# TopfieldClock.net
KiCad netlist of a schematic drawn in EAGLE
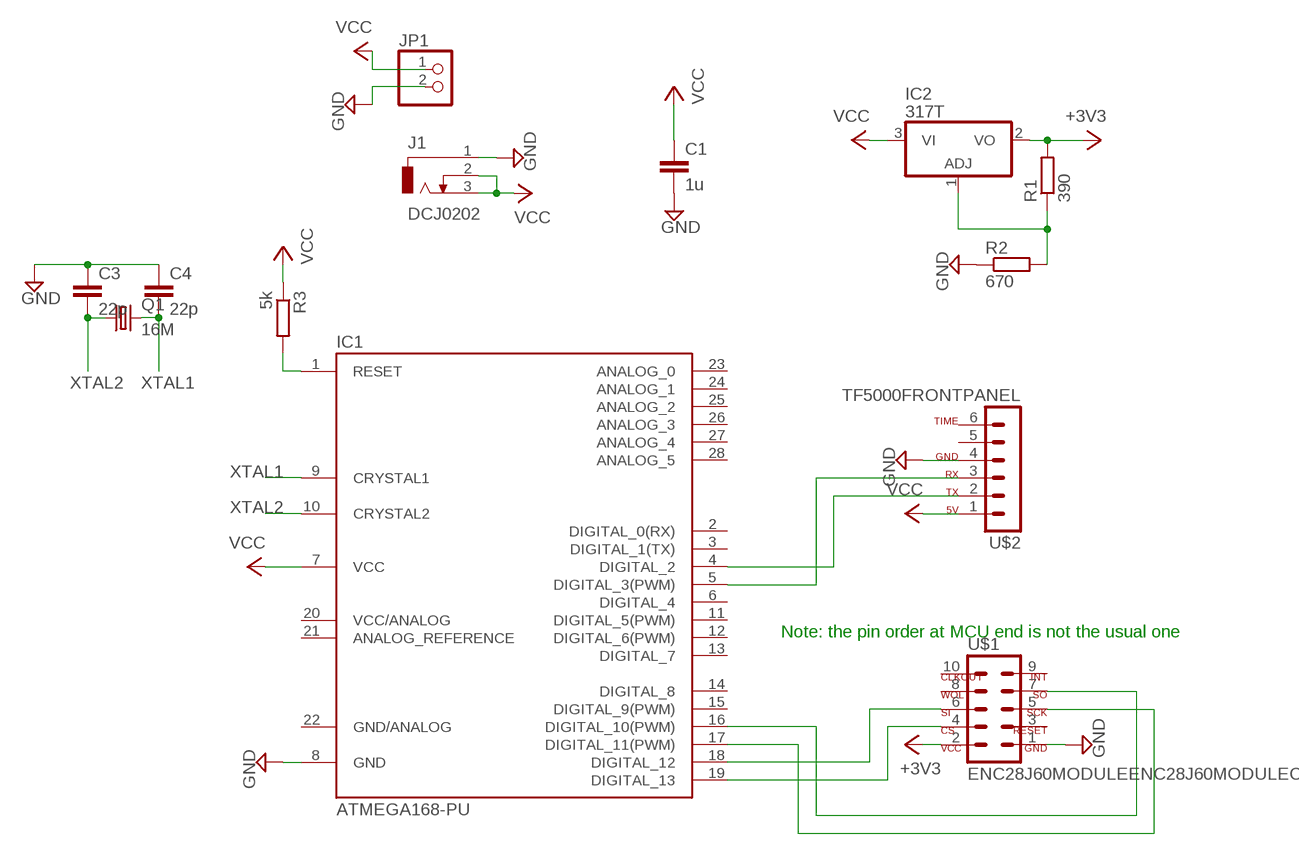
[diagram p0: schematic, sheet 1]

(export (version "E")
  (design (tool "Eeschema 10.0.6"))
  (components
    (comp (ref "C1")
      (value "1u")
      (footprint "eagle-import:C025-024X044")
      (libsource (lib "eagle-import") (part "C-EU025-024X044"))
    )
    (comp (ref "C3")
      (value "22p")
      (footprint "eagle-import:C025-024X044")
      (libsource (lib "eagle-import") (part "C-EU025-024X044"))
    )
    (comp (ref "C4")
      (value "22p")
      (footprint "eagle-import:C025-024X044")
      (libsource (lib "eagle-import") (part "C-EU025-024X044"))
    )
    (comp (ref "IC1")
      (value "ATMEGA168-PU")
      (footprint "eagle-import:DIL28-3")
      (libsource (lib "eagle-import") (part "ATMEGA168-PU"))
    )
    (comp (ref "IC2")
      (value "317T")
      (footprint "eagle-import:TO220H")
      (libsource (lib "eagle-import") (part "317T"))
    )
    (comp (ref "J1")
      (value "DCJ0202")
      (footprint "eagle-import:DCJ0202")
      (libsource (lib "eagle-import") (part "DCJ0202"))
    )
    (comp (ref "JP1")
      (value "PINHD-1X2/90")
      (footprint "eagle-import:1X02_90")
      (libsource (lib "eagle-import") (part "PINHD-1X2/90"))
    )
    (comp (ref "Q1")
      (value "16M")
      (footprint "eagle-import:HC18U-V")
      (libsource (lib "eagle-import") (part "CRYSTALHC18U-V"))
    )
    (comp (ref "R1")
      (value "390")
      (footprint "eagle-import:0204_7")
      (libsource (lib "eagle-import") (part "R-EU_0204/7"))
    )
    (comp (ref "R2")
      (value "670")
      (footprint "eagle-import:0204_7")
      (libsource (lib "eagle-import") (part "R-EU_0204/7"))
    )
    (comp (ref "R3")
      (value "5k")
      (footprint "eagle-import:0204_7")
      (libsource (lib "eagle-import") (part "R-EU_0204/7"))
    )
    (comp (ref "U$1")
      (value "ENC28J60MODULEENC28J60MODULECONN")
      (footprint "eagle-import:ENC28J60MODULECONN")
      (libsource (lib "eagle-import") (part "ENC28J60MODULEENC28J60MODULECONN"))
    )
    (comp (ref "U$2")
      (value "TF5000FRONTPANEL")
      (footprint "eagle-import:MA06-1")
      (libsource (lib "eagle-import") (part "TF5000FRONTPANEL"))
    )
  )
  (nets
    (net (code "1") (name "+3V3") (class "Default")
      (node (ref "IC2") (pin "2") (pinfunction "VO_2") (pintype "passive"))
      (node (ref "R1") (pin "2") (pinfunction "2_2") (pintype "passive"))
      (node (ref "U$1") (pin "2") (pinfunction "VCC_2") (pintype "passive"))
    )
    (net (code "2") (name "/GND{slash}ANALOG") (class "Default")
      (node (ref "IC1") (pin "22") (pinfunction "GND/ANALOG_22") (pintype "power_in"))
    )
    (net (code "3") (name "/XTAL1") (class "Default")
      (node (ref "C4") (pin "2") (pinfunction "2_2") (pintype "passive"))
      (node (ref "IC1") (pin "9") (pinfunction "CRYSTAL1_9") (pintype "bidirectional"))
      (node (ref "Q1") (pin "2") (pinfunction "2_2") (pintype "passive"))
    )
    (net (code "4") (name "/XTAL2") (class "Default")
      (node (ref "C3") (pin "2") (pinfunction "2_2") (pintype "passive"))
      (node (ref "IC1") (pin "10") (pinfunction "CRYSTAL2_10") (pintype "bidirectional"))
      (node (ref "Q1") (pin "1") (pinfunction "1_1") (pintype "passive"))
    )
    (net (code "5") (name "GND") (class "Default")
      (node (ref "C1") (pin "2") (pinfunction "2_2") (pintype "passive"))
      (node (ref "C3") (pin "1") (pinfunction "1_1") (pintype "passive"))
      (node (ref "C4") (pin "1") (pinfunction "1_1") (pintype "passive"))
      (node (ref "IC1") (pin "8") (pinfunction "GND_8") (pintype "power_in"))
      (node (ref "J1") (pin "1") (pinfunction "1_1") (pintype "passive"))
      (node (ref "JP1") (pin "2") (pinfunction "2_2") (pintype "passive"))
      (node (ref "R2") (pin "1") (pinfunction "1_1") (pintype "passive"))
      (node (ref "U$1") (pin "1") (pinfunction "GND_1") (pintype "passive"))
      (node (ref "U$2") (pin "4") (pinfunction "YELLOW_GND_4") (pintype "passive"))
    )
    (net (code "6") (name "Net-(IC1-DIGITAL_2)") (class "Default")
      (node (ref "IC1") (pin "4") (pinfunction "DIGITAL_2_4") (pintype "bidirectional"))
      (node (ref "U$2") (pin "2") (pinfunction "RED_OUTPUT_2") (pintype "passive"))
    )
    (net (code "7") (name "Net-(IC1-DIGITAL_3(PWM))") (class "Default")
      (node (ref "IC1") (pin "5") (pinfunction "DIGITAL_3(PWM)_5") (pintype "bidirectional"))
      (node (ref "U$2") (pin "3") (pinfunction "ORANGE_INPUT_3") (pintype "passive"))
    )
    (net (code "8") (name "Net-(IC1-DIGITAL_10(PWM))") (class "Default")
      (node (ref "IC1") (pin "16") (pinfunction "DIGITAL_10(PWM)_16") (pintype "bidirectional"))
      (node (ref "U$1") (pin "7") (pinfunction "SO_7") (pintype "passive"))
    )
    (net (code "9") (name "Net-(IC1-DIGITAL_11(PWM))") (class "Default")
      (node (ref "IC1") (pin "17") (pinfunction "DIGITAL_11(PWM)_17") (pintype "bidirectional"))
      (node (ref "U$1") (pin "5") (pinfunction "SCK_5") (pintype "passive"))
    )
    (net (code "10") (name "Net-(IC1-DIGITAL_12)") (class "Default")
      (node (ref "IC1") (pin "18") (pinfunction "DIGITAL_12_18") (pintype "bidirectional"))
      (node (ref "U$1") (pin "6") (pinfunction "SI_6") (pintype "passive"))
    )
    (net (code "11") (name "Net-(IC1-DIGITAL_13)") (class "Default")
      (node (ref "IC1") (pin "19") (pinfunction "DIGITAL_13_19") (pintype "bidirectional"))
      (node (ref "U$1") (pin "4") (pinfunction "CS_4") (pintype "passive"))
    )
    (net (code "12") (name "Net-(IC1-RESET)") (class "Default")
      (node (ref "IC1") (pin "1") (pinfunction "RESET_1") (pintype "bidirectional"))
      (node (ref "R3") (pin "2") (pinfunction "2_2") (pintype "passive"))
    )
    (net (code "13") (name "Net-(IC2-ADJ)") (class "Default")
      (node (ref "IC2") (pin "1") (pinfunction "ADJ_1") (pintype "input"))
      (node (ref "R1") (pin "1") (pinfunction "1_1") (pintype "passive"))
      (node (ref "R2") (pin "2") (pinfunction "2_2") (pintype "passive"))
    )
    (net (code "14") (name "VCC") (class "Default")
      (node (ref "C1") (pin "1") (pinfunction "1_1") (pintype "passive"))
      (node (ref "IC1") (pin "7") (pinfunction "VCC_7") (pintype "power_in"))
      (node (ref "IC2") (pin "3") (pinfunction "VI_3") (pintype "input"))
      (node (ref "J1") (pin "2") (pinfunction "2_2") (pintype "passive"))
      (node (ref "J1") (pin "3") (pinfunction "3_3") (pintype "passive"))
      (node (ref "JP1") (pin "1") (pinfunction "1_1") (pintype "passive"))
      (node (ref "R3") (pin "1") (pinfunction "1_1") (pintype "passive"))
      (node (ref "U$2") (pin "1") (pinfunction "BROWN_5V_1") (pintype "passive"))
    )
    (net (code "15") (name "unconnected-(IC1-ANALOG_0-Pad23)") (class "Default")
      (node (ref "IC1") (pin "23") (pinfunction "ANALOG_0_23") (pintype "bidirectional"))
    )
    (net (code "16") (name "unconnected-(IC1-ANALOG_1-Pad24)") (class "Default")
      (node (ref "IC1") (pin "24") (pinfunction "ANALOG_1_24") (pintype "bidirectional"))
    )
    (net (code "17") (name "unconnected-(IC1-ANALOG_2-Pad25)") (class "Default")
      (node (ref "IC1") (pin "25") (pinfunction "ANALOG_2_25") (pintype "bidirectional"))
    )
    (net (code "18") (name "unconnected-(IC1-ANALOG_3-Pad26)") (class "Default")
      (node (ref "IC1") (pin "26") (pinfunction "ANALOG_3_26") (pintype "bidirectional"))
    )
    (net (code "19") (name "unconnected-(IC1-ANALOG_4-Pad27)") (class "Default")
      (node (ref "IC1") (pin "27") (pinfunction "ANALOG_4_27") (pintype "bidirectional"))
    )
    (net (code "20") (name "unconnected-(IC1-ANALOG_5-Pad28)") (class "Default")
      (node (ref "IC1") (pin "28") (pinfunction "ANALOG_5_28") (pintype "bidirectional"))
    )
    (net (code "21") (name "unconnected-(IC1-ANALOG_REFERENCE-Pad21)") (class "Default")
      (node (ref "IC1") (pin "21") (pinfunction "ANALOG_REFERENCE_21") (pintype "passive"))
    )
    (net (code "22") (name "unconnected-(IC1-DIGITAL_0(RX)-Pad2)") (class "Default")
      (node (ref "IC1") (pin "2") (pinfunction "DIGITAL_0(RX)_2") (pintype "bidirectional"))
    )
    (net (code "23") (name "unconnected-(IC1-DIGITAL_1(TX)-Pad3)") (class "Default")
      (node (ref "IC1") (pin "3") (pinfunction "DIGITAL_1(TX)_3") (pintype "bidirectional"))
    )
    (net (code "24") (name "unconnected-(IC1-DIGITAL_4-Pad6)") (class "Default")
      (node (ref "IC1") (pin "6") (pinfunction "DIGITAL_4_6") (pintype "bidirectional"))
    )
    (net (code "25") (name "unconnected-(IC1-DIGITAL_5(PWM)-Pad11)") (class "Default")
      (node (ref "IC1") (pin "11") (pinfunction "DIGITAL_5(PWM)_11") (pintype "bidirectional"))
    )
    (net (code "26") (name "unconnected-(IC1-DIGITAL_6(PWM)-Pad12)") (class "Default")
      (node (ref "IC1") (pin "12") (pinfunction "DIGITAL_6(PWM)_12") (pintype "bidirectional"))
    )
    (net (code "27") (name "unconnected-(IC1-DIGITAL_7-Pad13)") (class "Default")
      (node (ref "IC1") (pin "13") (pinfunction "DIGITAL_7_13") (pintype "bidirectional"))
    )
    (net (code "28") (name "unconnected-(IC1-DIGITAL_8-Pad14)") (class "Default")
      (node (ref "IC1") (pin "14") (pinfunction "DIGITAL_8_14") (pintype "bidirectional"))
    )
    (net (code "29") (name "unconnected-(IC1-DIGITAL_9(PWM)-Pad15)") (class "Default")
      (node (ref "IC1") (pin "15") (pinfunction "DIGITAL_9(PWM)_15") (pintype "bidirectional"))
    )
    (net (code "30") (name "unconnected-(IC1-VCC{slash}ANALOG-Pad20)") (class "Default")
      (node (ref "IC1") (pin "20") (pinfunction "VCC/ANALOG_20") (pintype "passive"))
    )
    (net (code "31") (name "unconnected-(U$1-CLKOUT-Pad10)") (class "Default")
      (node (ref "U$1") (pin "10") (pinfunction "CLKOUT_10") (pintype "passive"))
    )
    (net (code "32") (name "unconnected-(U$1-INT-Pad9)") (class "Default")
      (node (ref "U$1") (pin "9") (pinfunction "INT_9") (pintype "passive"))
    )
    (net (code "33") (name "unconnected-(U$1-RESET-Pad3)") (class "Default")
      (node (ref "U$1") (pin "3") (pinfunction "RESET_3") (pintype "passive"))
    )
    (net (code "34") (name "unconnected-(U$1-WOL-Pad8)") (class "Default")
      (node (ref "U$1") (pin "8") (pinfunction "WOL_8") (pintype "passive"))
    )
    (net (code "35") (name "unconnected-(U$2-BLUE_TIME-Pad6)") (class "Default")
      (node (ref "U$2") (pin "6") (pinfunction "BLUE_TIME_6") (pintype "passive"))
    )
    (net (code "36") (name "unconnected-(U$2-GREEN-Pad5)") (class "Default")
      (node (ref "U$2") (pin "5") (pinfunction "GREEN_5") (pintype "passive"))
    )
  )
)
